# BMS-Shield_rev2.net
KiCad netlist of a schematic drawn in EAGLE
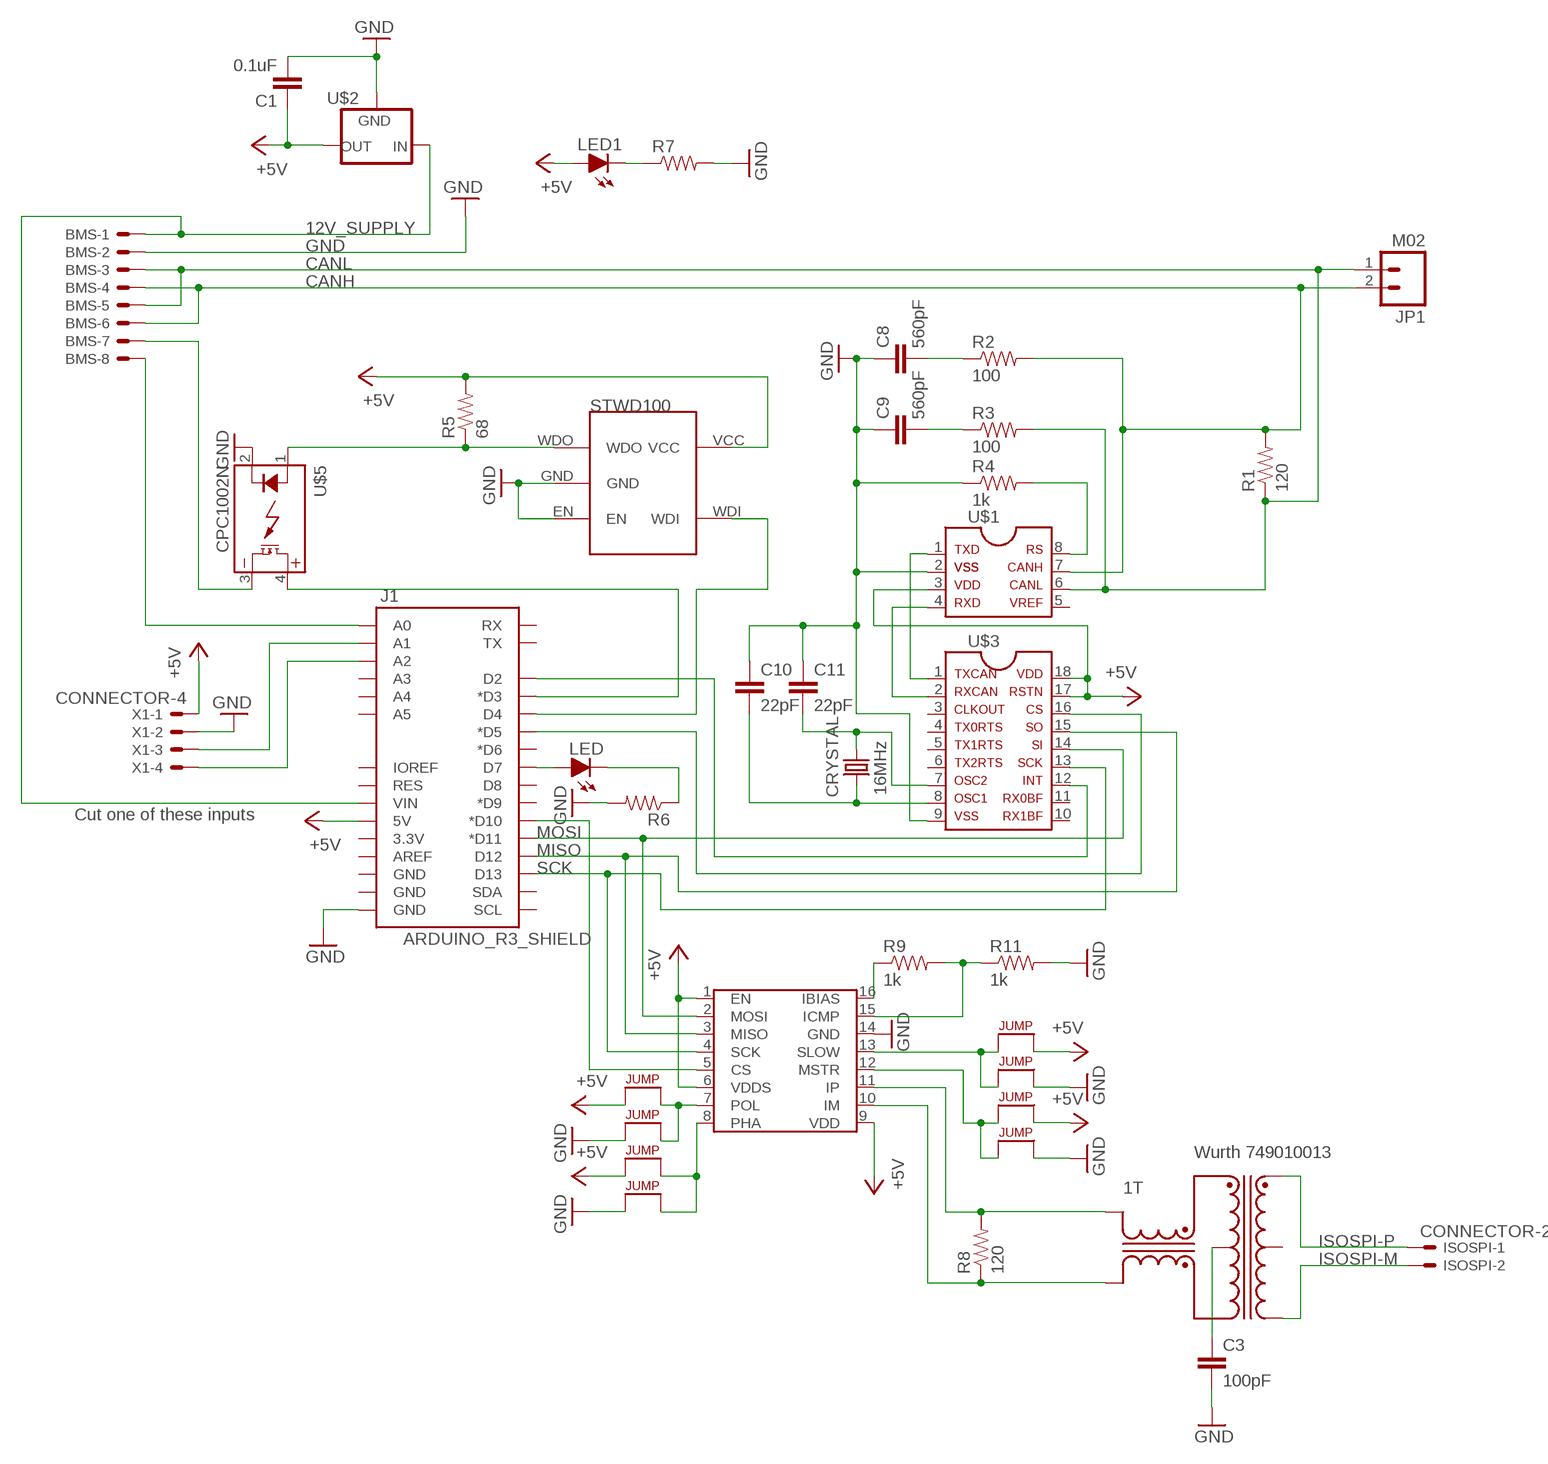
[diagram p0: schematic, sheet 1]

(export (version "E")
  (design (tool "Eeschema 10.0.6"))
  (components
    (comp (ref "1")
      (value "TRANSFORMER_749010013")
      (footprint "eagle-import:749010013")
      (libsource (lib "eagle-import") (part "TRANSFORMER_749010013"))
    )
    (comp (ref "BMS")
      (value "MINIFIT_5566-8")
      (footprint "eagle-import:MINIFIT_5566-8")
      (libsource (lib "eagle-import") (part "MINIFIT_5566-8"))
    )
    (comp (ref "C1")
      (value "0.1uF")
      (footprint "eagle-import:0805")
      (libsource (lib "eagle-import") (part "CAP0805"))
    )
    (comp (ref "C3")
      (value "100pF")
      (footprint "eagle-import:0805")
      (libsource (lib "eagle-import") (part "CAP0805"))
    )
    (comp (ref "C8")
      (value "560pF")
      (footprint "eagle-import:0805")
      (libsource (lib "eagle-import") (part "CAP0805"))
    )
    (comp (ref "C9")
      (value "560pF")
      (footprint "eagle-import:0805")
      (libsource (lib "eagle-import") (part "CAP0805"))
    )
    (comp (ref "C10")
      (value "22pF")
      (footprint "eagle-import:0805")
      (libsource (lib "eagle-import") (part "CAP0805"))
    )
    (comp (ref "C11")
      (value "22pF")
      (footprint "eagle-import:0805")
      (libsource (lib "eagle-import") (part "CAP0805"))
    )
    (comp (ref "CRYSTAL")
      (value "16MHz")
      (footprint "eagle-import:HC49UP")
      (libsource (lib "eagle-import") (part "CRYSTALSMD"))
    )
    (comp (ref "ISOSPI")
      (value "CONNECTOR-2")
      (footprint "eagle-import:MINIFIT_5566-2")
      (libsource (lib "eagle-import") (part "CONNECTOR-2"))
    )
    (comp (ref "J1")
      (value "ARDUINO_R3_SHIELD")
      (footprint "eagle-import:UNO_R3_SHIELD")
      (libsource (lib "eagle-import") (part "ARDUINO_R3_SHIELD"))
    )
    (comp (ref "JP1")
      (value "M02")
      (footprint "eagle-import:1X02")
      (libsource (lib "eagle-import") (part "M02"))
    )
    (comp (ref "LED")
      (value "LED-0805")
      (footprint "eagle-import:LED-805")
      (libsource (lib "eagle-import") (part "LED-0805"))
    )
    (comp (ref "LED1")
      (value "LED-0805")
      (footprint "eagle-import:LED-805")
      (libsource (lib "eagle-import") (part "LED-0805"))
    )
    (comp (ref "R1")
      (value "120")
      (footprint "eagle-import:0805")
      (libsource (lib "eagle-import") (part "RESISTOR0805-RES"))
    )
    (comp (ref "R2")
      (value "100")
      (footprint "eagle-import:0805")
      (libsource (lib "eagle-import") (part "RESISTOR0805-RES"))
    )
    (comp (ref "R3")
      (value "100")
      (footprint "eagle-import:0805")
      (libsource (lib "eagle-import") (part "RESISTOR0805-RES"))
    )
    (comp (ref "R4")
      (value "1k")
      (footprint "eagle-import:0805")
      (libsource (lib "eagle-import") (part "RESISTOR0805-RES"))
    )
    (comp (ref "R5")
      (value "68")
      (footprint "eagle-import:0805")
      (libsource (lib "eagle-import") (part "RESISTOR0805-RES"))
    )
    (comp (ref "R6")
      (value "RESISTOR0805-RES")
      (footprint "eagle-import:0805")
      (libsource (lib "eagle-import") (part "RESISTOR0805-RES"))
    )
    (comp (ref "R7")
      (value "RESISTOR0805-RES")
      (footprint "eagle-import:0805")
      (libsource (lib "eagle-import") (part "RESISTOR0805-RES"))
    )
    (comp (ref "R8")
      (value "120")
      (footprint "eagle-import:0805")
      (libsource (lib "eagle-import") (part "RESISTOR0805-RES"))
    )
    (comp (ref "R9")
      (value "1k")
      (footprint "eagle-import:0805")
      (libsource (lib "eagle-import") (part "RESISTOR0805-RES"))
    )
    (comp (ref "R11")
      (value "1k")
      (footprint "eagle-import:0805")
      (libsource (lib "eagle-import") (part "RESISTOR0805-RES"))
    )
    (comp (ref "U$1")
      (value "MCP2551")
      (footprint "eagle-import:SOIC-08")
      (libsource (lib "eagle-import") (part "MCP2551"))
    )
    (comp (ref "U$2")
      (value "5VREG_LM340-NLM340MPX-5.0/NOPB")
      (footprint "eagle-import:SOT223")
      (libsource (lib "eagle-import") (part "5VREG_LM340-NLM340MPX-5.0/NOPB"))
    )
    (comp (ref "U$3")
      (value "MCP2515SMD")
      (footprint "eagle-import:SOIC-18W")
      (libsource (lib "eagle-import") (part "MCP2515SMD"))
    )
    (comp (ref "U$4")
      (value "STWD100")
      (footprint "eagle-import:SOT23-5")
      (libsource (lib "eagle-import") (part "STWD100"))
    )
    (comp (ref "U$5")
      (value "CPC1002N")
      (footprint "eagle-import:SOP04")
      (libsource (lib "eagle-import") (part "CPC1002N"))
    )
    (comp (ref "U$6")
      (value "LTC6820")
      (footprint "eagle-import:MSOP-16")
      (libsource (lib "eagle-import") (part "LTC6820"))
    )
    (comp (ref "U$7")
      (value "JUMPER")
      (footprint "eagle-import:0805")
      (libsource (lib "eagle-import") (part "JUMPER"))
    )
    (comp (ref "U$8")
      (value "JUMPER")
      (footprint "eagle-import:0805")
      (libsource (lib "eagle-import") (part "JUMPER"))
    )
    (comp (ref "U$9")
      (value "JUMPER")
      (footprint "eagle-import:0805")
      (libsource (lib "eagle-import") (part "JUMPER"))
    )
    (comp (ref "U$10")
      (value "JUMPER")
      (footprint "eagle-import:0805")
      (libsource (lib "eagle-import") (part "JUMPER"))
    )
    (comp (ref "U$11")
      (value "JUMPER")
      (footprint "eagle-import:0805")
      (libsource (lib "eagle-import") (part "JUMPER"))
    )
    (comp (ref "U$12")
      (value "JUMPER")
      (footprint "eagle-import:0805")
      (libsource (lib "eagle-import") (part "JUMPER"))
    )
    (comp (ref "U$13")
      (value "JUMPER")
      (footprint "eagle-import:0805")
      (libsource (lib "eagle-import") (part "JUMPER"))
    )
    (comp (ref "U$14")
      (value "JUMPER")
      (footprint "eagle-import:0805")
      (libsource (lib "eagle-import") (part "JUMPER"))
    )
    (comp (ref "X1")
      (value "CONNECTOR-4")
      (footprint "eagle-import:MINIFIT_5566-4")
      (libsource (lib "eagle-import") (part "CONNECTOR-4"))
    )
  )
  (nets
    (net (code "1") (name "+5V") (class "Default")
      (node (ref "C1") (pin "1") (pinfunction "1_1") (pintype "passive"))
      (node (ref "J1") (pin "5V") (pinfunction "5V_5V") (pintype "bidirectional"))
      (node (ref "LED1") (pin "A") (pinfunction "A_A") (pintype "passive"))
      (node (ref "R5") (pin "2") (pinfunction "2_2") (pintype "passive"))
      (node (ref "U$1") (pin "3") (pinfunction "3_3") (pintype "passive"))
      (node (ref "U$10") (pin "1") (pinfunction "P$1_1") (pintype "bidirectional"))
      (node (ref "U$11") (pin "2") (pinfunction "P$2_2") (pintype "bidirectional"))
      (node (ref "U$13") (pin "2") (pinfunction "P$2_2") (pintype "bidirectional"))
      (node (ref "U$2") (pin "3") (pinfunction "OUT_3") (pintype "output"))
      (node (ref "U$3") (pin "17") (pinfunction "17_17") (pintype "passive"))
      (node (ref "U$3") (pin "18") (pinfunction "18_18") (pintype "passive"))
      (node (ref "U$4") (pin "VCC") (pinfunction "VCC_VCC") (pintype "bidirectional"))
      (node (ref "U$6") (pin "1") (pinfunction "EN_1") (pintype "bidirectional"))
      (node (ref "U$6") (pin "6") (pinfunction "VDDS_6") (pintype "bidirectional"))
      (node (ref "U$6") (pin "9") (pinfunction "VDD_9") (pintype "bidirectional"))
      (node (ref "U$7") (pin "1") (pinfunction "P$1_1") (pintype "bidirectional"))
      (node (ref "X1") (pin "1") (pinfunction "S_1") (pintype "passive"))
    )
    (net (code "2") (name "/12V_SUPPLY") (class "Default")
      (node (ref "BMS") (pin "1") (pinfunction "S_1") (pintype "passive"))
      (node (ref "J1") (pin "VIN") (pinfunction "VIN_VIN") (pintype "bidirectional"))
      (node (ref "U$2") (pin "1") (pinfunction "IN_1") (pintype "input"))
    )
    (net (code "3") (name "/CANH") (class "Default")
      (node (ref "BMS") (pin "4") (pinfunction "S_4") (pintype "passive"))
      (node (ref "BMS") (pin "6") (pinfunction "S_6") (pintype "passive"))
      (node (ref "JP1") (pin "2") (pinfunction "2_2") (pintype "passive"))
      (node (ref "R1") (pin "2") (pinfunction "2_2") (pintype "passive"))
      (node (ref "R2") (pin "2") (pinfunction "2_2") (pintype "passive"))
      (node (ref "U$1") (pin "7") (pinfunction "7_7") (pintype "passive"))
    )
    (net (code "4") (name "/CANL") (class "Default")
      (node (ref "BMS") (pin "3") (pinfunction "S_3") (pintype "passive"))
      (node (ref "BMS") (pin "5") (pinfunction "S_5") (pintype "passive"))
      (node (ref "JP1") (pin "1") (pinfunction "1_1") (pintype "passive"))
      (node (ref "R1") (pin "1") (pinfunction "1_1") (pintype "passive"))
      (node (ref "R3") (pin "2") (pinfunction "2_2") (pintype "passive"))
      (node (ref "U$1") (pin "6") (pinfunction "6_6") (pintype "passive"))
    )
    (net (code "5") (name "/ISOSPI-M") (class "Default")
      (node (ref "1") (pin "3") (pinfunction "D-_3") (pintype "passive"))
      (node (ref "ISOSPI") (pin "2") (pinfunction "S_2") (pintype "passive"))
    )
    (net (code "6") (name "/ISOSPI-P") (class "Default")
      (node (ref "1") (pin "1") (pinfunction "D+_1") (pintype "passive"))
      (node (ref "ISOSPI") (pin "1") (pinfunction "S_1") (pintype "passive"))
    )
    (net (code "7") (name "/MISO") (class "Default")
      (node (ref "J1") (pin "D12") (pinfunction "D12_D12") (pintype "bidirectional"))
      (node (ref "U$3") (pin "15") (pinfunction "15_15") (pintype "passive"))
      (node (ref "U$6") (pin "3") (pinfunction "MISO_3") (pintype "bidirectional"))
    )
    (net (code "8") (name "/MOSI") (class "Default")
      (node (ref "J1") (pin "D11") (pinfunction "*D11_D11") (pintype "bidirectional"))
      (node (ref "U$3") (pin "14") (pinfunction "14_14") (pintype "passive"))
      (node (ref "U$6") (pin "2") (pinfunction "MOSI_2") (pintype "bidirectional"))
    )
    (net (code "9") (name "/SCK") (class "Default")
      (node (ref "J1") (pin "D13") (pinfunction "D13_D13") (pintype "bidirectional"))
      (node (ref "U$3") (pin "13") (pinfunction "13_13") (pintype "passive"))
      (node (ref "U$6") (pin "4") (pinfunction "SCK_4") (pintype "bidirectional"))
    )
    (net (code "10") (name "GND") (class "Default")
      (node (ref "BMS") (pin "2") (pinfunction "S_2") (pintype "passive"))
      (node (ref "C1") (pin "2") (pinfunction "2_2") (pintype "passive"))
      (node (ref "C10") (pin "1") (pinfunction "1_1") (pintype "passive"))
      (node (ref "C11") (pin "1") (pinfunction "1_1") (pintype "passive"))
      (node (ref "C3") (pin "2") (pinfunction "2_2") (pintype "passive"))
      (node (ref "C8") (pin "1") (pinfunction "1_1") (pintype "passive"))
      (node (ref "C9") (pin "1") (pinfunction "1_1") (pintype "passive"))
      (node (ref "J1") (pin "GND@0") (pinfunction "GND_GND@0") (pintype "bidirectional"))
      (node (ref "R11") (pin "2") (pinfunction "2_2") (pintype "passive"))
      (node (ref "R4") (pin "1") (pinfunction "1_1") (pintype "passive"))
      (node (ref "R6") (pin "2") (pinfunction "2_2") (pintype "passive"))
      (node (ref "R7") (pin "2") (pinfunction "2_2") (pintype "passive"))
      (node (ref "U$1") (pin "2") (pinfunction "2_2") (pintype "passive"))
      (node (ref "U$12") (pin "2") (pinfunction "P$2_2") (pintype "bidirectional"))
      (node (ref "U$14") (pin "2") (pinfunction "P$2_2") (pintype "bidirectional"))
      (node (ref "U$2") (pin "2") (pinfunction "GND_2") (pintype "input"))
      (node (ref "U$2") (pin "4") (pinfunction "GND_4") (pintype "input"))
      (node (ref "U$3") (pin "9") (pinfunction "9_9") (pintype "passive"))
      (node (ref "U$4") (pin "EN") (pinfunction "EN_EN") (pintype "bidirectional"))
      (node (ref "U$4") (pin "GND") (pinfunction "GND_GND") (pintype "bidirectional"))
      (node (ref "U$5") (pin "2") (pinfunction "CONTROL-_2") (pintype "passive"))
      (node (ref "U$6") (pin "14") (pinfunction "GND_14") (pintype "bidirectional"))
      (node (ref "U$8") (pin "1") (pinfunction "P$1_1") (pintype "bidirectional"))
      (node (ref "U$9") (pin "1") (pinfunction "P$1_1") (pintype "bidirectional"))
      (node (ref "X1") (pin "2") (pinfunction "S_2") (pintype "passive"))
    )
    (net (code "11") (name "Net-(1B-CX)") (class "Default")
      (node (ref "1") (pin "15") (pinfunction "CX_15") (pintype "passive"))
      (node (ref "C3") (pin "1") (pinfunction "1_1") (pintype "passive"))
    )
    (net (code "12") (name "Net-(1B-X+)") (class "Default")
      (node (ref "1") (pin "16") (pinfunction "X+_16") (pintype "passive"))
      (node (ref "R8") (pin "2") (pinfunction "2_2") (pintype "passive"))
      (node (ref "U$6") (pin "11") (pinfunction "IP_11") (pintype "bidirectional"))
    )
    (net (code "13") (name "Net-(1B-X-)") (class "Default")
      (node (ref "1") (pin "14") (pinfunction "X-_14") (pintype "passive"))
      (node (ref "R8") (pin "1") (pinfunction "1_1") (pintype "passive"))
      (node (ref "U$6") (pin "10") (pinfunction "IM_10") (pintype "bidirectional"))
    )
    (net (code "14") (name "Net-(BMSG-S)") (class "Default")
      (node (ref "BMS") (pin "7") (pinfunction "S_7") (pintype "passive"))
      (node (ref "U$5") (pin "3") (pinfunction "DC-_3") (pintype "passive"))
    )
    (net (code "15") (name "Net-(BMSH-S)") (class "Default")
      (node (ref "BMS") (pin "8") (pinfunction "S_8") (pintype "passive"))
      (node (ref "J1") (pin "A0") (pinfunction "A0_A0") (pintype "bidirectional"))
    )
    (net (code "16") (name "Net-(C8-Pad2)") (class "Default")
      (node (ref "C8") (pin "2") (pinfunction "2_2") (pintype "passive"))
      (node (ref "R2") (pin "1") (pinfunction "1_1") (pintype "passive"))
    )
    (net (code "17") (name "Net-(C9-Pad2)") (class "Default")
      (node (ref "C9") (pin "2") (pinfunction "2_2") (pintype "passive"))
      (node (ref "R3") (pin "1") (pinfunction "1_1") (pintype "passive"))
    )
    (net (code "18") (name "Net-(C10-Pad2)") (class "Default")
      (node (ref "C10") (pin "2") (pinfunction "2_2") (pintype "passive"))
      (node (ref "CRYSTAL") (pin "2") (pinfunction "2_2") (pintype "passive"))
      (node (ref "U$3") (pin "8") (pinfunction "8_8") (pintype "passive"))
    )
    (net (code "19") (name "Net-(C11-Pad2)") (class "Default")
      (node (ref "C11") (pin "2") (pinfunction "2_2") (pintype "passive"))
      (node (ref "CRYSTAL") (pin "1") (pinfunction "1_1") (pintype "passive"))
      (node (ref "U$3") (pin "7") (pinfunction "7_7") (pintype "passive"))
    )
    (net (code "20") (name "Net-(J1-*D3)") (class "Default")
      (node (ref "J1") (pin "D3") (pinfunction "*D3_D3") (pintype "bidirectional"))
      (node (ref "U$5") (pin "4") (pinfunction "DC+_4") (pintype "passive"))
    )
    (net (code "21") (name "Net-(J1-*D5)") (class "Default")
      (node (ref "J1") (pin "D5") (pinfunction "*D5_D5") (pintype "bidirectional"))
      (node (ref "U$3") (pin "16") (pinfunction "16_16") (pintype "passive"))
    )
    (net (code "22") (name "Net-(J1-*D10)") (class "Default")
      (node (ref "J1") (pin "D10") (pinfunction "*D10_D10") (pintype "bidirectional"))
      (node (ref "U$6") (pin "5") (pinfunction "CS_5") (pintype "bidirectional"))
    )
    (net (code "23") (name "Net-(J1-PadD2)") (class "Default")
      (node (ref "J1") (pin "D2") (pinfunction "D2_D2") (pintype "bidirectional"))
      (node (ref "U$3") (pin "12") (pinfunction "12_12") (pintype "passive"))
    )
    (net (code "24") (name "Net-(J1-PadD4)") (class "Default")
      (node (ref "J1") (pin "D4") (pinfunction "D4_D4") (pintype "bidirectional"))
      (node (ref "U$4") (pin "WDI") (pinfunction "WDI_WDI") (pintype "bidirectional"))
    )
    (net (code "25") (name "Net-(J1-PadD7)") (class "Default")
      (node (ref "J1") (pin "D7") (pinfunction "D7_D7") (pintype "bidirectional"))
      (node (ref "LED") (pin "A") (pinfunction "A_A") (pintype "passive"))
    )
    (net (code "26") (name "Net-(LED-PadC)") (class "Default")
      (node (ref "LED") (pin "C") (pinfunction "C_C") (pintype "passive"))
      (node (ref "R6") (pin "1") (pinfunction "1_1") (pintype "passive"))
    )
    (net (code "27") (name "Net-(LED1-PadC)") (class "Default")
      (node (ref "LED1") (pin "C") (pinfunction "C_C") (pintype "passive"))
      (node (ref "R7") (pin "1") (pinfunction "1_1") (pintype "passive"))
    )
    (net (code "28") (name "Net-(R4-Pad2)") (class "Default")
      (node (ref "R4") (pin "2") (pinfunction "2_2") (pintype "passive"))
      (node (ref "U$1") (pin "8") (pinfunction "8_8") (pintype "passive"))
    )
    (net (code "29") (name "Net-(U$1-Pad1)") (class "Default")
      (node (ref "U$1") (pin "1") (pinfunction "1_1") (pintype "passive"))
      (node (ref "U$3") (pin "1") (pinfunction "1_1") (pintype "passive"))
    )
    (net (code "30") (name "Net-(U$1-Pad4)") (class "Default")
      (node (ref "U$1") (pin "4") (pinfunction "4_4") (pintype "passive"))
      (node (ref "U$3") (pin "2") (pinfunction "2_2") (pintype "passive"))
    )
    (net (code "31") (name "Net-(U$5-CONTROL+)") (class "Default")
      (node (ref "R5") (pin "1") (pinfunction "1_1") (pintype "passive"))
      (node (ref "U$4") (pin "WDO") (pinfunction "WDO_WDO") (pintype "bidirectional"))
      (node (ref "U$5") (pin "1") (pinfunction "CONTROL+_1") (pintype "passive"))
    )
    (net (code "32") (name "Net-(U$6-IBIAS)") (class "Default")
      (node (ref "R9") (pin "1") (pinfunction "1_1") (pintype "passive"))
      (node (ref "U$6") (pin "16") (pinfunction "IBIAS_16") (pintype "bidirectional"))
    )
    (net (code "33") (name "Net-(U$6-ICMP)") (class "Default")
      (node (ref "R11") (pin "1") (pinfunction "1_1") (pintype "passive"))
      (node (ref "R9") (pin "2") (pinfunction "2_2") (pintype "passive"))
      (node (ref "U$6") (pin "15") (pinfunction "ICMP_15") (pintype "bidirectional"))
    )
    (net (code "34") (name "Net-(U$6-POL)") (class "Default")
      (node (ref "U$6") (pin "7") (pinfunction "POL_7") (pintype "bidirectional"))
      (node (ref "U$7") (pin "2") (pinfunction "P$2_2") (pintype "bidirectional"))
      (node (ref "U$8") (pin "2") (pinfunction "P$2_2") (pintype "bidirectional"))
    )
    (net (code "35") (name "Net-(U$10-P$2)") (class "Default")
      (node (ref "U$10") (pin "2") (pinfunction "P$2_2") (pintype "bidirectional"))
      (node (ref "U$6") (pin "8") (pinfunction "PHA_8") (pintype "bidirectional"))
      (node (ref "U$9") (pin "2") (pinfunction "P$2_2") (pintype "bidirectional"))
    )
    (net (code "36") (name "Net-(U$11-P$1)") (class "Default")
      (node (ref "U$11") (pin "1") (pinfunction "P$1_1") (pintype "bidirectional"))
      (node (ref "U$12") (pin "1") (pinfunction "P$1_1") (pintype "bidirectional"))
      (node (ref "U$6") (pin "13") (pinfunction "SLOW_13") (pintype "bidirectional"))
    )
    (net (code "37") (name "Net-(U$13-P$1)") (class "Default")
      (node (ref "U$13") (pin "1") (pinfunction "P$1_1") (pintype "bidirectional"))
      (node (ref "U$14") (pin "1") (pinfunction "P$1_1") (pintype "bidirectional"))
      (node (ref "U$6") (pin "12") (pinfunction "MSTR_12") (pintype "bidirectional"))
    )
    (net (code "38") (name "Net-(X1C-S)") (class "Default")
      (node (ref "J1") (pin "A1") (pinfunction "A1_A1") (pintype "bidirectional"))
      (node (ref "X1") (pin "3") (pinfunction "S_3") (pintype "passive"))
    )
    (net (code "39") (name "Net-(X1D-S)") (class "Default")
      (node (ref "J1") (pin "A2") (pinfunction "A2_A2") (pintype "bidirectional"))
      (node (ref "X1") (pin "4") (pinfunction "S_4") (pintype "passive"))
    )
    (net (code "40") (name "unconnected-(1B-CD-Pad2)") (class "Default")
      (node (ref "1") (pin "2") (pinfunction "CD_2") (pintype "passive"))
    )
    (net (code "41") (name "unconnected-(J1-*D6-PadD6)") (class "Default")
      (node (ref "J1") (pin "D6") (pinfunction "*D6_D6") (pintype "bidirectional"))
    )
    (net (code "42") (name "unconnected-(J1-*D9-PadD9)") (class "Default")
      (node (ref "J1") (pin "D9") (pinfunction "*D9_D9") (pintype "bidirectional"))
    )
    (net (code "43") (name "unconnected-(J1-GND-PadGND@1)") (class "Default")
      (node (ref "J1") (pin "GND@1") (pinfunction "GND_GND@1") (pintype "bidirectional"))
    )
    (net (code "44") (name "unconnected-(J1-GND-PadGND@2)") (class "Default")
      (node (ref "J1") (pin "GND@2") (pinfunction "GND_GND@2") (pintype "bidirectional"))
    )
    (net (code "45") (name "unconnected-(J1-Pad3.3V)") (class "Default")
      (node (ref "J1") (pin "3.3V") (pinfunction "3.3V_3.3V") (pintype "bidirectional"))
    )
    (net (code "46") (name "unconnected-(J1-PadA3)") (class "Default")
      (node (ref "J1") (pin "A3") (pinfunction "A3_A3") (pintype "bidirectional"))
    )
    (net (code "47") (name "unconnected-(J1-PadA4)") (class "Default")
      (node (ref "J1") (pin "A4") (pinfunction "A4_A4") (pintype "bidirectional"))
    )
    (net (code "48") (name "unconnected-(J1-PadA5)") (class "Default")
      (node (ref "J1") (pin "A5") (pinfunction "A5_A5") (pintype "bidirectional"))
    )
    (net (code "49") (name "unconnected-(J1-PadAREF)") (class "Default")
      (node (ref "J1") (pin "AREF") (pinfunction "AREF_AREF") (pintype "bidirectional"))
    )
    (net (code "50") (name "unconnected-(J1-PadD8)") (class "Default")
      (node (ref "J1") (pin "D8") (pinfunction "D8_D8") (pintype "bidirectional"))
    )
    (net (code "51") (name "unconnected-(J1-PadIOREF)") (class "Default")
      (node (ref "J1") (pin "IOREF") (pinfunction "IOREF_IOREF") (pintype "bidirectional"))
    )
    (net (code "52") (name "unconnected-(J1-PadRES)") (class "Default")
      (node (ref "J1") (pin "RES") (pinfunction "RES_RES") (pintype "bidirectional"))
    )
    (net (code "53") (name "unconnected-(J1-PadRX)") (class "Default")
      (node (ref "J1") (pin "RX") (pinfunction "RX_RX") (pintype "bidirectional"))
    )
    (net (code "54") (name "unconnected-(J1-PadSCL)") (class "Default")
      (node (ref "J1") (pin "SCL") (pinfunction "SCL_SCL") (pintype "bidirectional"))
    )
    (net (code "55") (name "unconnected-(J1-PadSDA)") (class "Default")
      (node (ref "J1") (pin "SDA") (pinfunction "SDA_SDA") (pintype "bidirectional"))
    )
    (net (code "56") (name "unconnected-(J1-PadTX)") (class "Default")
      (node (ref "J1") (pin "TX") (pinfunction "TX_TX") (pintype "bidirectional"))
    )
    (net (code "57") (name "unconnected-(U$1-Pad5)") (class "Default")
      (node (ref "U$1") (pin "5") (pinfunction "5_5") (pintype "passive"))
    )
    (net (code "58") (name "unconnected-(U$3-Pad3)") (class "Default")
      (node (ref "U$3") (pin "3") (pinfunction "3_3") (pintype "passive"))
    )
    (net (code "59") (name "unconnected-(U$3-Pad4)") (class "Default")
      (node (ref "U$3") (pin "4") (pinfunction "4_4") (pintype "passive"))
    )
    (net (code "60") (name "unconnected-(U$3-Pad5)") (class "Default")
      (node (ref "U$3") (pin "5") (pinfunction "5_5") (pintype "passive"))
    )
    (net (code "61") (name "unconnected-(U$3-Pad6)") (class "Default")
      (node (ref "U$3") (pin "6") (pinfunction "6_6") (pintype "passive"))
    )
    (net (code "62") (name "unconnected-(U$3-Pad10)") (class "Default")
      (node (ref "U$3") (pin "10") (pinfunction "10_10") (pintype "passive"))
    )
    (net (code "63") (name "unconnected-(U$3-Pad11)") (class "Default")
      (node (ref "U$3") (pin "11") (pinfunction "11_11") (pintype "passive"))
    )
  )
)
